# 403_5MHz_LNA.net
KiCad netlist of a schematic drawn in Altium Designer
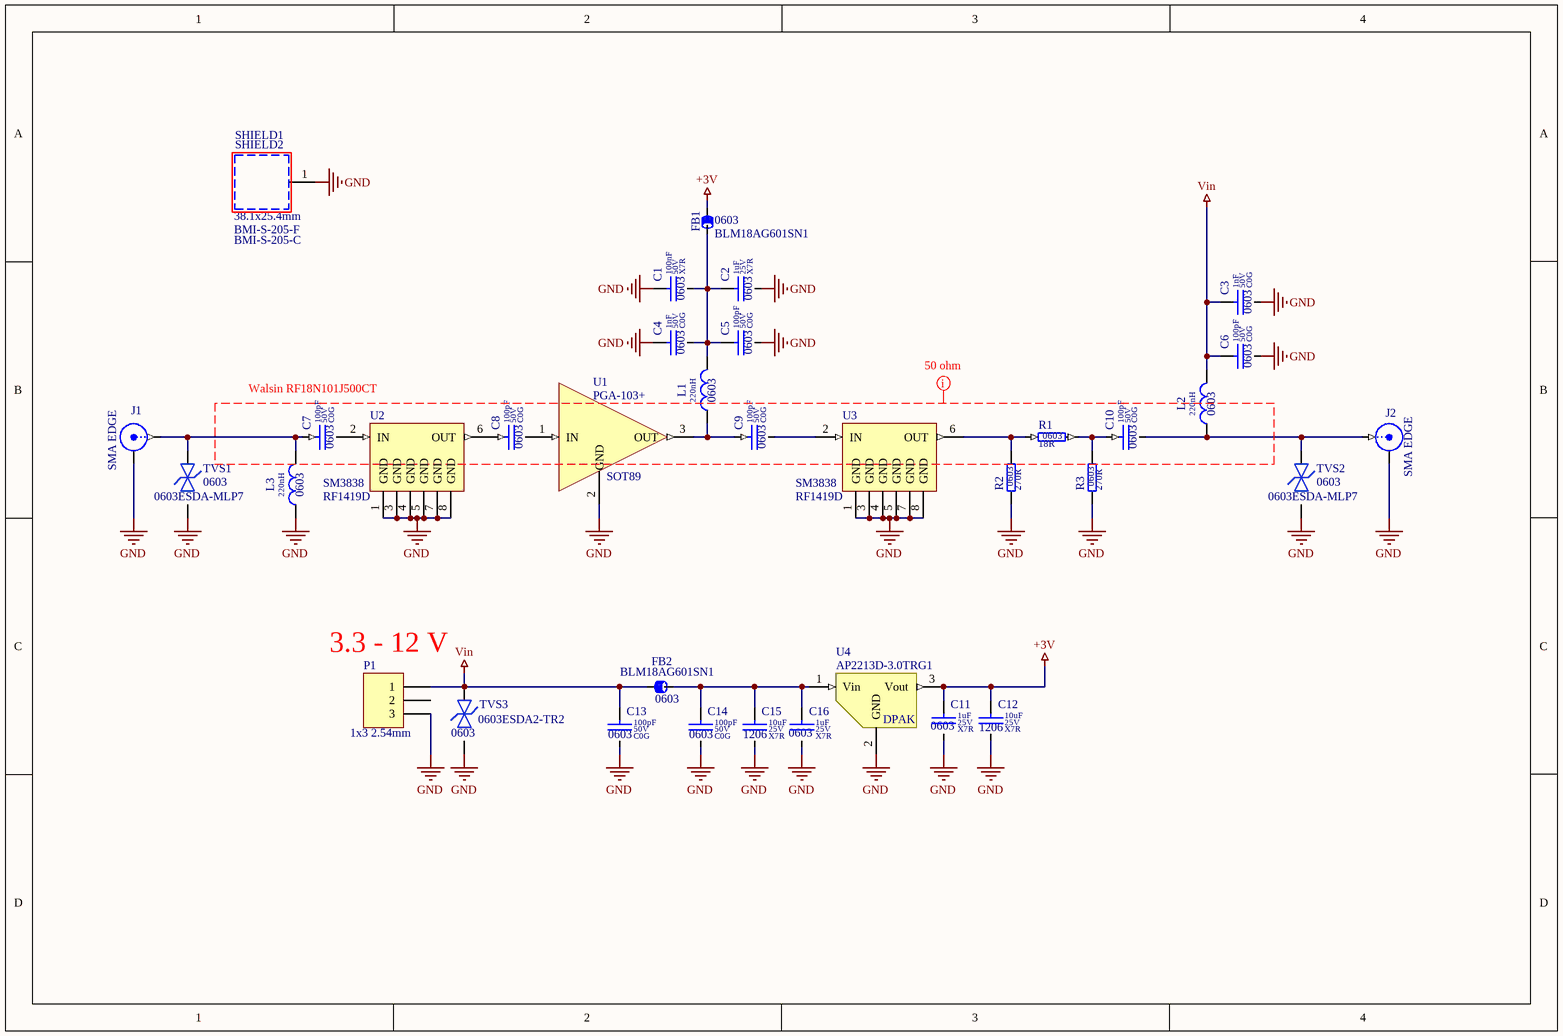
[diagram p0: 403.5MHz_LNA.SchDoc]

(export (version "E")
  (design (tool "Eeschema 10.0.6"))
  (components
    (comp (ref "C1")
      (value "100nF")
      (footprint "C_0603_1608")
      (description "Capacitor")
      (fields
        (field (name "DIELECTRIC") "X7R")
        (field (name "VOLTAGE") "50V")
        (field (name "SCH_FOOTPRINT") "0603")
        (field (name "PART NUMBER") "C_100nF_50V_X7R_0603_5")
        (field (name "MANUFACTURER") "Samsung")
      )
      (libsource (lib "") (part "C_1"))
    )
    (comp (ref "C2")
      (value "1uF")
      (footprint "C_0603_1608")
      (description "Capacitor")
      (fields
        (field (name "DIELECTRIC") "X7R")
        (field (name "VOLTAGE") "25V")
        (field (name "SCH_FOOTPRINT") "0603")
        (field (name "PART NUMBER") "C_1uF_25V_X7R_0603_10")
        (field (name "MANUFACTURER") "Samsung")
      )
      (libsource (lib "") (part "C_1"))
    )
    (comp (ref "C3")
      (value "1nF")
      (footprint "C_0603_1608")
      (description "Capacitor")
      (fields
        (field (name "DIELECTRIC") "C0G")
        (field (name "VOLTAGE") "50V")
        (field (name "SCH_FOOTPRINT") "0603")
        (field (name "PART NUMBER") "C_1nF_50V_C0G_0603_5")
        (field (name "MANUFACTURER") "Samsung")
      )
      (libsource (lib "") (part "C_1"))
    )
    (comp (ref "C4")
      (value "1nF")
      (footprint "C_0603_1608")
      (description "Capacitor")
      (fields
        (field (name "DIELECTRIC") "C0G")
        (field (name "VOLTAGE") "50V")
        (field (name "SCH_FOOTPRINT") "0603")
        (field (name "PART NUMBER") "C_1nF_50V_C0G_0603_5")
        (field (name "MANUFACTURER") "Samsung")
      )
      (libsource (lib "") (part "C_1"))
    )
    (comp (ref "C5")
      (value "100pF")
      (footprint "C_0603_1608")
      (description "Capacitor")
      (fields
        (field (name "DIELECTRIC") "C0G")
        (field (name "VOLTAGE") "50V")
        (field (name "SCH_FOOTPRINT") "0603")
        (field (name "PART NUMBER") "C_100pF_50V_C0G_0603_5")
        (field (name "MANUFACTURER") "Walsin")
      )
      (libsource (lib "") (part "C_1"))
    )
    (comp (ref "C6")
      (value "100pF")
      (footprint "C_0603_1608")
      (description "Capacitor")
      (fields
        (field (name "DIELECTRIC") "C0G")
        (field (name "VOLTAGE") "50V")
        (field (name "SCH_FOOTPRINT") "0603")
        (field (name "PART NUMBER") "C_100pF_50V_C0G_0603_5")
        (field (name "MANUFACTURER") "Walsin")
      )
      (libsource (lib "") (part "C_1"))
    )
    (comp (ref "C7")
      (value "100pF")
      (footprint "C_0603_1608")
      (description "Capacitor")
      (fields
        (field (name "DIELECTRIC") "C0G")
        (field (name "VOLTAGE") "50V")
        (field (name "SCH_FOOTPRINT") "0603")
        (field (name "PART NUMBER") "C_100pF_50V_C0G_0603_5")
        (field (name "MANUFACTURER") "Walsin")
      )
      (libsource (lib "Library") (part "C"))
    )
    (comp (ref "C8")
      (value "100pF")
      (footprint "C_0603_1608")
      (description "Capacitor")
      (fields
        (field (name "DIELECTRIC") "C0G")
        (field (name "VOLTAGE") "50V")
        (field (name "SCH_FOOTPRINT") "0603")
        (field (name "PART NUMBER") "C_100pF_50V_C0G_0603_5")
        (field (name "MANUFACTURER") "Walsin")
      )
      (libsource (lib "Library") (part "C"))
    )
    (comp (ref "C9")
      (value "100pF")
      (footprint "C_0603_1608")
      (description "Capacitor")
      (fields
        (field (name "DIELECTRIC") "C0G")
        (field (name "VOLTAGE") "50V")
        (field (name "SCH_FOOTPRINT") "0603")
        (field (name "PART NUMBER") "C_100pF_50V_C0G_0603_5")
        (field (name "MANUFACTURER") "Walsin")
      )
      (libsource (lib "Library") (part "C"))
    )
    (comp (ref "C10")
      (value "100pF")
      (footprint "C_0603_1608")
      (description "Capacitor")
      (fields
        (field (name "DIELECTRIC") "C0G")
        (field (name "VOLTAGE") "50V")
        (field (name "SCH_FOOTPRINT") "0603")
        (field (name "PART NUMBER") "C_100pF_50V_C0G_0603_5")
        (field (name "MANUFACTURER") "Walsin")
      )
      (libsource (lib "Library") (part "C"))
    )
    (comp (ref "C11")
      (value "1uF")
      (footprint "C_0603_1608")
      (description "Capacitor")
      (fields
        (field (name "DIELECTRIC") "X7R")
        (field (name "VOLTAGE") "25V")
        (field (name "SCH_FOOTPRINT") "0603")
        (field (name "PART NUMBER") "C_1uF_25V_X7R_0603_10")
        (field (name "MANUFACTURER") "Samsung")
      )
      (libsource (lib "") (part "C_1"))
    )
    (comp (ref "C12")
      (value "10uF")
      (footprint "C_1206_3216")
      (description "Capacitor")
      (fields
        (field (name "DIELECTRIC") "X7R")
        (field (name "VOLTAGE") "25V")
        (field (name "SCH_FOOTPRINT") "1206")
        (field (name "PART NUMBER") "C_10uF_25V_X7R_1206_10")
        (field (name "MANUFACTURER") "Samsung Electro-Mechanics")
      )
      (libsource (lib "") (part "C_1"))
    )
    (comp (ref "C13")
      (value "100pF")
      (footprint "C_0603_1608")
      (description "Capacitor")
      (fields
        (field (name "DIELECTRIC") "C0G")
        (field (name "VOLTAGE") "50V")
        (field (name "SCH_FOOTPRINT") "0603")
        (field (name "PART NUMBER") "C_100pF_50V_C0G_0603_5")
        (field (name "MANUFACTURER") "Walsin")
      )
      (libsource (lib "") (part "C_1"))
    )
    (comp (ref "C14")
      (value "100pF")
      (footprint "C_0603_1608")
      (description "Capacitor")
      (fields
        (field (name "DIELECTRIC") "C0G")
        (field (name "VOLTAGE") "50V")
        (field (name "SCH_FOOTPRINT") "0603")
        (field (name "PART NUMBER") "C_100pF_50V_C0G_0603_5")
        (field (name "MANUFACTURER") "Walsin")
      )
      (libsource (lib "") (part "C_1"))
    )
    (comp (ref "C15")
      (value "10uF")
      (footprint "C_1206_3216")
      (description "Capacitor")
      (fields
        (field (name "DIELECTRIC") "X7R")
        (field (name "VOLTAGE") "25V")
        (field (name "SCH_FOOTPRINT") "1206")
        (field (name "PART NUMBER") "C_10uF_25V_X7R_1206_10")
        (field (name "MANUFACTURER") "Samsung Electro-Mechanics")
      )
      (libsource (lib "") (part "C_1"))
    )
    (comp (ref "C16")
      (value "1uF")
      (footprint "C_0603_1608")
      (description "Capacitor")
      (fields
        (field (name "DIELECTRIC") "X7R")
        (field (name "VOLTAGE") "25V")
        (field (name "SCH_FOOTPRINT") "0603")
        (field (name "PART NUMBER") "C_1uF_25V_X7R_0603_10")
        (field (name "MANUFACTURER") "Samsung")
      )
      (libsource (lib "") (part "C_1"))
    )
    (comp (ref "FB1")
      (value "BLM18AG601SN1")
      (footprint "FB_0603_1608")
      (description "Ferrite Bead")
      (fields
        (field (name "PART NUMBER") "FB_BLM18AG601SN1")
        (field (name "SCH_FOOTPRINT") "0603")
        (field (name "MANUFACTURER") "Murata")
      )
      (libsource (lib "") (part "FB_1"))
    )
    (comp (ref "FB2")
      (value "BLM18AG601SN1")
      (footprint "FB_0603_1608")
      (description "Ferrite Bead")
      (fields
        (field (name "PART NUMBER") "FB_BLM18AG601SN1")
        (field (name "SCH_FOOTPRINT") "0603")
        (field (name "MANUFACTURER") "Murata")
      )
      (libsource (lib "Library") (part "FB"))
    )
    (comp (ref "J1")
      (value "SMA EDGE")
      (footprint "J_SMA_EDGE_6.25")
      (description "SMA connector")
      (fields
        (field (name "PART NUMBER") "J_SMA_EDGE_6.25")
        (field (name "SCH_FOOTPRINT") "SMA EDGE")
        (field (name "MANUFACTURER") "Adam Tech")
      )
      (libsource (lib "Library") (part "J_SMA"))
    )
    (comp (ref "J2")
      (value "SMA EDGE")
      (footprint "J_SMA_EDGE_6.25")
      (description "SMA connector")
      (fields
        (field (name "PART NUMBER") "J_SMA_EDGE_6.25")
        (field (name "SCH_FOOTPRINT") "SMA EDGE")
        (field (name "MANUFACTURER") "Adam Tech")
      )
      (libsource (lib "") (part "J_SMA_1"))
    )
    (comp (ref "L1")
      (value "220nH")
      (footprint "L_0603_1608")
      (description "Induction")
      (fields
        (field (name "SCH_FOOTPRINT") "0603")
        (field (name "PART NUMBER") "L_220nH_120mA_0603")
        (field (name "MANUFACTURER") "Murata")
      )
      (libsource (lib "Library") (part "L"))
    )
    (comp (ref "L2")
      (value "220nH")
      (footprint "L_0603_1608")
      (description "Induction")
      (fields
        (field (name "SCH_FOOTPRINT") "0603")
        (field (name "PART NUMBER") "L_220nH_120mA_0603")
        (field (name "MANUFACTURER") "Murata")
      )
      (libsource (lib "Library") (part "L"))
    )
    (comp (ref "L3")
      (value "220nH")
      (footprint "L_0603_1608")
      (description "Induction")
      (fields
        (field (name "SCH_FOOTPRINT") "0603")
        (field (name "PART NUMBER") "L_220nH_120mA_0603")
        (field (name "MANUFACTURER") "Murata")
      )
      (libsource (lib "Library") (part "L"))
    )
    (comp (ref "P1")
      (value "Goldpin")
      (footprint "P_HEADER_1x3_2.54")
      (description "Header, 3-Pin")
      (fields
        (field (name "PART NUMBER") "P_HEADER_1x3_2.54")
        (field (name "SCH_FOOTPRINT") "1x3 2.54mm")
        (field (name "MANUFACTURER") "Connfly")
      )
      (libsource (lib "Library") (part "P_HEADER_1x3"))
    )
    (comp (ref "R1")
      (value "18R")
      (footprint "R_NC_0603_1608")
      (fields
        (field (name "SCH_FOOTPRINT") "0603")
        (field (name "PART NUMBER") "R_GENERIC_0603")
        (field (name "Comment") "Resistor")
      )
      (libsource (lib "") (part "R_1"))
    )
    (comp (ref "R2")
      (value "270R")
      (footprint "R_NC_0603_1608")
      (fields
        (field (name "SCH_FOOTPRINT") "0603")
        (field (name "PART NUMBER") "R_GENERIC_0603")
        (field (name "Comment") "Resistor")
      )
      (libsource (lib "Library") (part "R"))
    )
    (comp (ref "R3")
      (value "270R")
      (footprint "R_NC_0603_1608")
      (fields
        (field (name "SCH_FOOTPRINT") "0603")
        (field (name "PART NUMBER") "R_GENERIC_0603")
        (field (name "Comment") "Resistor")
      )
      (libsource (lib "Library") (part "R"))
    )
    (comp (ref "SHIELD1")
      (value "BMI-S-205-C")
      (footprint "BMI-S-205-C")
      (description "Shield, 1 pad")
      (fields (field (name "PART NUMBER") "SHIELD_BMI-S-205-C") (field (name "MANUFACTURER") "Laird"))
      (libsource (lib "Library") (part "SHIELD_COVER"))
    )
    (comp (ref "SHIELD2")
      (value "BMI-S-205-F")
      (footprint "BMI-S-205-F")
      (description "Shield, 1 pad")
      (fields
        (field (name "PART NUMBER") "SHIELD_BMI-S-205-F")
        (field (name "SCH_FOOTPRINT") "38.1x25.4mm")
        (field (name "MANUFACTURER") "Laird")
      )
      (libsource (lib "Library") (part "SHIELD"))
    )
    (comp (ref "TVS1")
      (value "0603ESDA-MLP7")
      (footprint "R_0603_1608")
      (fields
        (field (name "SCH_FOOTPRINT") "0603")
        (field (name "PART NUMBER") "TVS_0603ESDA-MLP7")
        (field (name "VOLTAGE") "30V")
        (field (name "MANUFACTURER") "Bussmann")
      )
      (libsource (lib "Library") (part "TVS_BI"))
    )
    (comp (ref "TVS2")
      (value "0603ESDA-MLP7")
      (footprint "R_0603_1608")
      (fields
        (field (name "SCH_FOOTPRINT") "0603")
        (field (name "PART NUMBER") "TVS_0603ESDA-MLP7")
        (field (name "VOLTAGE") "30V")
        (field (name "MANUFACTURER") "Bussmann")
      )
      (libsource (lib "Library") (part "TVS_BI"))
    )
    (comp (ref "TVS3")
      (value "0603ESDA2-TR2")
      (footprint "R_0603_1608")
      (fields
        (field (name "SCH_FOOTPRINT") "0603")
        (field (name "PART NUMBER") "TVS_0603ESDA2")
        (field (name "VOLTAGE") "14V")
        (field (name "MANUFACTURER") "Bussmann")
      )
      (libsource (lib "Library") (part "TVS_BI"))
    )
    (comp (ref "U1")
      (value "PGA-103+")
      (footprint "SOT89_TO-243AA_N")
      (fields
        (field (name "PART NUMBER") "U_PGA103+")
        (field (name "SCH_FOOTPRINT") "SOT89")
        (field (name "MANUFACTURER") "Mini-Circuits")
        (field (name "Comment") "PGA103+")
      )
      (libsource (lib "Library") (part "U_PGA103+"))
    )
    (comp (ref "U2")
      (value "RF1419D")
      (footprint "SAW_QCC8B_SM3838-8_3.8x3.8")
      (fields
        (field (name "PART NUMBER") "U_RF1419D")
        (field (name "SCH_FOOTPRINT") "SM3838")
        (field (name "MANUFACTURER") "Murata")
      )
      (libsource (lib "Library") (part "U_SAW8_2_6"))
    )
    (comp (ref "U3")
      (value "RF1419D")
      (footprint "SAW_QCC8B_SM3838-8_3.8x3.8")
      (fields
        (field (name "PART NUMBER") "U_RF1419D")
        (field (name "SCH_FOOTPRINT") "SM3838")
        (field (name "MANUFACTURER") "Murata")
      )
      (libsource (lib "Library") (part "U_SAW8_2_6"))
    )
    (comp (ref "U4")
      (value "AP2213D-3.0TRG1")
      (footprint "DPAK_TO252-3_SC63_M")
      (fields
        (field (name "PART NUMBER") "VL_AP2213D-3.0TRG1")
        (field (name "SCH_FOOTPRINT") "DPAK")
        (field (name "VOLTAGE") "3V")
        (field (name "MANUFACTURER") "Diodes Inc")
      )
      (libsource (lib "Library") (part "VL_3pin_typical_1_2_3"))
    )
  )
  (nets
    (net (code "1") (name "+3V") (class "Default")
      (node (ref "C11") (pin "1") (pinfunction "1_1") (pintype "passive"))
      (node (ref "C12") (pin "1") (pinfunction "1_1") (pintype "passive"))
      (node (ref "FB1") (pin "1") (pintype "input"))
      (node (ref "U4") (pin "3") (pinfunction "Vout_3") (pintype "output"))
    )
    (net (code "2") (name "GND") (class "Default")
      (node (ref "C1") (pin "1") (pinfunction "1_1") (pintype "passive"))
      (node (ref "C11") (pin "2") (pinfunction "2_2") (pintype "passive"))
      (node (ref "C12") (pin "2") (pinfunction "2_2") (pintype "passive"))
      (node (ref "C13") (pin "2") (pinfunction "2_2") (pintype "passive"))
      (node (ref "C14") (pin "2") (pinfunction "2_2") (pintype "passive"))
      (node (ref "C15") (pin "2") (pinfunction "2_2") (pintype "passive"))
      (node (ref "C16") (pin "2") (pinfunction "2_2") (pintype "passive"))
      (node (ref "C2") (pin "2") (pinfunction "2_2") (pintype "passive"))
      (node (ref "C3") (pin "2") (pinfunction "2_2") (pintype "passive"))
      (node (ref "C4") (pin "1") (pinfunction "1_1") (pintype "passive"))
      (node (ref "C5") (pin "2") (pinfunction "2_2") (pintype "passive"))
      (node (ref "C6") (pin "2") (pinfunction "2_2") (pintype "passive"))
      (node (ref "J1") (pin "2") (pinfunction "Y_2") (pintype "passive"))
      (node (ref "J2") (pin "2") (pinfunction "Y_2") (pintype "passive"))
      (node (ref "L3") (pin "1") (pinfunction "1_1") (pintype "passive"))
      (node (ref "P1") (pin "3") (pinfunction "3_3") (pintype "passive"))
      (node (ref "R2") (pin "1") (pinfunction "1_1") (pintype "passive"))
      (node (ref "R3") (pin "1") (pinfunction "1_1") (pintype "passive"))
      (node (ref "SHIELD2") (pin "1") (pinfunction "shield_1") (pintype "passive"))
      (node (ref "TVS1") (pin "2") (pinfunction "2_2") (pintype "passive"))
      (node (ref "TVS2") (pin "2") (pinfunction "2_2") (pintype "passive"))
      (node (ref "TVS3") (pin "2") (pinfunction "2_2") (pintype "passive"))
      (node (ref "U1") (pin "2") (pinfunction "GND_2") (pintype "power_in"))
      (node (ref "U2") (pin "1") (pinfunction "GND_1") (pintype "power_in"))
      (node (ref "U2") (pin "3") (pinfunction "GND_3") (pintype "power_in"))
      (node (ref "U2") (pin "4") (pinfunction "GND_4") (pintype "power_in"))
      (node (ref "U2") (pin "5") (pinfunction "GND_5") (pintype "power_in"))
      (node (ref "U2") (pin "7") (pinfunction "GND_7") (pintype "power_in"))
      (node (ref "U2") (pin "8") (pinfunction "GND_8") (pintype "power_in"))
      (node (ref "U3") (pin "1") (pinfunction "GND_1") (pintype "power_in"))
      (node (ref "U3") (pin "3") (pinfunction "GND_3") (pintype "power_in"))
      (node (ref "U3") (pin "4") (pinfunction "GND_4") (pintype "power_in"))
      (node (ref "U3") (pin "5") (pinfunction "GND_5") (pintype "power_in"))
      (node (ref "U3") (pin "7") (pinfunction "GND_7") (pintype "power_in"))
      (node (ref "U3") (pin "8") (pinfunction "GND_8") (pintype "power_in"))
      (node (ref "U4") (pin "2") (pinfunction "GND_2") (pintype "power_in"))
    )
    (net (code "3") (name "Net-(C1-Pad2)") (class "Default")
      (node (ref "C1") (pin "2") (pinfunction "2_2") (pintype "passive"))
      (node (ref "C2") (pin "1") (pinfunction "1_1") (pintype "passive"))
      (node (ref "C4") (pin "2") (pinfunction "2_2") (pintype "passive"))
      (node (ref "C5") (pin "1") (pinfunction "1_1") (pintype "passive"))
      (node (ref "FB1") (pin "2") (pintype "output"))
      (node (ref "L1") (pin "2") (pinfunction "2_2") (pintype "passive"))
    )
    (net (code "4") (name "Net-(C10-Pad1)") (class "Default")
      (node (ref "C10") (pin "1") (pinfunction "1_1") (pintype "input"))
      (node (ref "R1") (pin "2") (pinfunction "2_2") (pintype "output"))
      (node (ref "R3") (pin "2") (pinfunction "2_2") (pintype "passive"))
    )
    (net (code "5") (name "Net-(J1-X)") (class "Default")
      (node (ref "C7") (pin "1") (pinfunction "1_1") (pintype "input"))
      (node (ref "J1") (pin "1") (pinfunction "X_1") (pintype "output"))
      (node (ref "L3") (pin "2") (pinfunction "2_2") (pintype "passive"))
      (node (ref "TVS1") (pin "1") (pinfunction "1_1") (pintype "passive"))
    )
    (net (code "6") (name "Net-(J2-X)") (class "Default")
      (node (ref "C10") (pin "2") (pinfunction "2_2") (pintype "output"))
      (node (ref "J2") (pin "1") (pinfunction "X_1") (pintype "input"))
      (node (ref "L2") (pin "1") (pinfunction "1_1") (pintype "passive"))
      (node (ref "TVS2") (pin "1") (pinfunction "1_1") (pintype "passive"))
    )
    (net (code "7") (name "Net-(U1-IN)") (class "Default")
      (node (ref "C8") (pin "2") (pinfunction "2_2") (pintype "output"))
      (node (ref "U1") (pin "1") (pinfunction "IN_1") (pintype "input"))
    )
    (net (code "8") (name "Net-(U1-OUT)") (class "Default")
      (node (ref "C9") (pin "1") (pinfunction "1_1") (pintype "input"))
      (node (ref "L1") (pin "1") (pinfunction "1_1") (pintype "passive"))
      (node (ref "U1") (pin "3") (pinfunction "OUT_3") (pintype "output"))
    )
    (net (code "9") (name "Net-(U2-IN)") (class "Default")
      (node (ref "C7") (pin "2") (pinfunction "2_2") (pintype "output"))
      (node (ref "U2") (pin "2") (pinfunction "IN_2") (pintype "input"))
    )
    (net (code "10") (name "Net-(U2-OUT)") (class "Default")
      (node (ref "C8") (pin "1") (pinfunction "1_1") (pintype "input"))
      (node (ref "U2") (pin "6") (pinfunction "OUT_6") (pintype "output"))
    )
    (net (code "11") (name "Net-(U3-IN)") (class "Default")
      (node (ref "C9") (pin "2") (pinfunction "2_2") (pintype "output"))
      (node (ref "U3") (pin "2") (pinfunction "IN_2") (pintype "input"))
    )
    (net (code "12") (name "Net-(U3-OUT)") (class "Default")
      (node (ref "R1") (pin "1") (pinfunction "1_1") (pintype "input"))
      (node (ref "R2") (pin "2") (pinfunction "2_2") (pintype "passive"))
      (node (ref "U3") (pin "6") (pinfunction "OUT_6") (pintype "output"))
    )
    (net (code "13") (name "Net-(U4-Vin)") (class "Default")
      (node (ref "C14") (pin "1") (pinfunction "1_1") (pintype "passive"))
      (node (ref "C15") (pin "1") (pinfunction "1_1") (pintype "passive"))
      (node (ref "C16") (pin "1") (pinfunction "1_1") (pintype "passive"))
      (node (ref "FB2") (pin "2") (pintype "output"))
      (node (ref "U4") (pin "1") (pinfunction "Vin_1") (pintype "input"))
    )
    (net (code "14") (name "Vin") (class "Default")
      (node (ref "C13") (pin "1") (pinfunction "1_1") (pintype "passive"))
      (node (ref "C3") (pin "1") (pinfunction "1_1") (pintype "passive"))
      (node (ref "C6") (pin "1") (pinfunction "1_1") (pintype "passive"))
      (node (ref "FB2") (pin "1") (pintype "input"))
      (node (ref "L2") (pin "2") (pinfunction "2_2") (pintype "passive"))
      (node (ref "P1") (pin "1") (pinfunction "1_1") (pintype "passive"))
      (node (ref "TVS3") (pin "1") (pinfunction "1_1") (pintype "passive"))
    )
    (net (code "15") (name "unconnected-(P1-Pad2)") (class "Default")
      (node (ref "P1") (pin "2") (pinfunction "2_2") (pintype "passive"))
    )
  )
)
